# encoder-mjf.net
KiCad netlist of a schematic drawn in Altium Designer
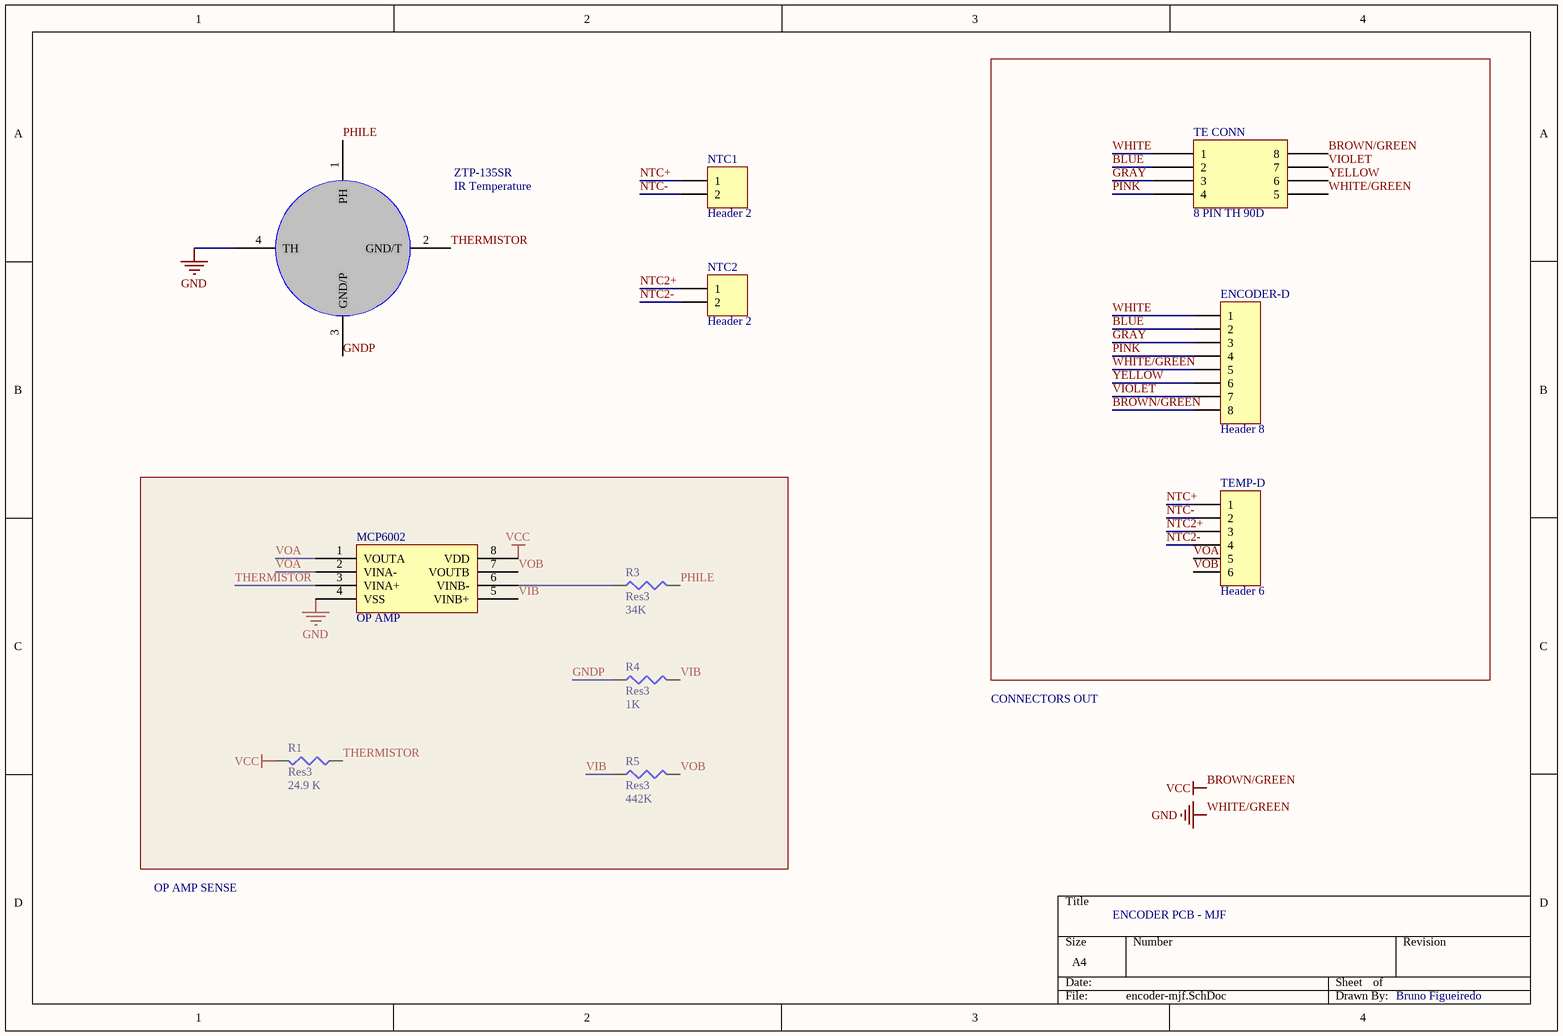
[diagram p0: encoder-mjf.SchDoc]

(export (version "E")
  (design (tool "Eeschema 10.0.6"))
  (components
    (comp (ref "ENCODER-D")
      (value "Header 8")
      (footprint "HDR1X8")
      (description "Header, 8-Pin")
      (fields (field (name "PUBLISHER") "Altium Limited"))
      (libsource (lib "Miscellaneous Connectors") (part "Header 8"))
    )
    (comp (ref "MCP6002")
      (value "OP AMP")
      (footprint "DIP-8")
      (libsource (lib "encoder-mjf") (part "MCP6002-I/P"))
    )
    (comp (ref "NTC1")
      (value "Header 2")
      (footprint "HDR1X2")
      (description "Header, 2-Pin")
      (fields (field (name "PUBLISHER") "Altium Limited"))
      (libsource (lib "Miscellaneous Connectors") (part "Header 2"))
    )
    (comp (ref "NTC2")
      (value "Header 2")
      (footprint "HDR1X2")
      (description "Header, 2-Pin")
      (fields (field (name "PUBLISHER") "Altium Limited"))
      (libsource (lib "Miscellaneous Connectors") (part "Header 2"))
    )
    (comp (ref "R1")
      (value "Res3")
      (footprint "J1-0603")
      (description "Resistor")
      (fields (field (name "ALTIUM_VALUE") "24.9 K") (field (name "PUBLISHER") "Altium Limited"))
      (libsource (lib "Miscellaneous Devices") (part "Res3"))
    )
    (comp (ref "R3")
      (value "Res3")
      (footprint "J1-0603")
      (description "Resistor")
      (fields (field (name "ALTIUM_VALUE") "34K") (field (name "PUBLISHER") "Altium Limited"))
      (libsource (lib "Miscellaneous Devices") (part "Res3"))
    )
    (comp (ref "R4")
      (value "Res3")
      (footprint "J1-0603")
      (description "Resistor")
      (fields (field (name "ALTIUM_VALUE") "1K") (field (name "PUBLISHER") "Altium Limited"))
      (libsource (lib "Miscellaneous Devices") (part "Res3"))
    )
    (comp (ref "R5")
      (value "Res3")
      (footprint "C1206")
      (description "Resistor")
      (fields (field (name "ALTIUM_VALUE") "442K") (field (name "PUBLISHER") "Altium Limited"))
      (libsource (lib "Miscellaneous Devices") (part "Res3"))
    )
    (comp (ref "TE CONN")
      (value "8 PIN TH 90D")
      (footprint "NG_CD_2172077")
      (libsource (lib "encoder-mjf") (part "NG-CD-2172077"))
    )
    (comp (ref "TEMP-D")
      (value "Header 6")
      (footprint "HDR1X6")
      (description "Header, 6-Pin")
      (fields (field (name "PUBLISHER") "Altium Limited"))
      (libsource (lib "Miscellaneous Connectors") (part "Header 6"))
    )
    (comp (ref "ZTP-135SR")
      (value "IR Temperature")
      (footprint "ZTP-135SR")
      (description "Thermistor + Thermophile")
      (libsource (lib "encoder-mjf") (part "ZTP-135SR"))
    )
  )
  (nets
    (net (code "1") (name "/BLUE") (class "Default")
      (node (ref "ENCODER-D") (pin "2") (pinfunction "2_2") (pintype "passive"))
      (node (ref "TE CONN") (pin "2") (pinfunction "2_2") (pintype "passive"))
    )
    (net (code "2") (name "/GNDP") (class "Default")
      (node (ref "R4") (pin "1") (pinfunction "1_1") (pintype "passive"))
      (node (ref "ZTP-135SR") (pin "3") (pinfunction "GND/P_3") (pintype "passive"))
    )
    (net (code "3") (name "/GRAY") (class "Default")
      (node (ref "ENCODER-D") (pin "3") (pinfunction "3_3") (pintype "passive"))
      (node (ref "TE CONN") (pin "3") (pinfunction "3_3") (pintype "passive"))
    )
    (net (code "4") (name "/NTC+") (class "Default")
      (node (ref "NTC1") (pin "1") (pinfunction "1_1") (pintype "passive"))
      (node (ref "TEMP-D") (pin "1") (pinfunction "1_1") (pintype "passive"))
    )
    (net (code "5") (name "/NTC-") (class "Default")
      (node (ref "NTC1") (pin "2") (pinfunction "2_2") (pintype "passive"))
      (node (ref "TEMP-D") (pin "2") (pinfunction "2_2") (pintype "passive"))
    )
    (net (code "6") (name "/NTC2+") (class "Default")
      (node (ref "NTC2") (pin "1") (pinfunction "1_1") (pintype "passive"))
      (node (ref "TEMP-D") (pin "3") (pinfunction "3_3") (pintype "passive"))
    )
    (net (code "7") (name "/NTC2-") (class "Default")
      (node (ref "NTC2") (pin "2") (pinfunction "2_2") (pintype "passive"))
      (node (ref "TEMP-D") (pin "4") (pinfunction "4_4") (pintype "passive"))
    )
    (net (code "8") (name "/PHILE") (class "Default")
      (node (ref "R3") (pin "2") (pinfunction "2_2") (pintype "passive"))
      (node (ref "ZTP-135SR") (pin "1") (pinfunction "PH_1") (pintype "passive"))
    )
    (net (code "9") (name "/PINK") (class "Default")
      (node (ref "ENCODER-D") (pin "4") (pinfunction "4_4") (pintype "passive"))
      (node (ref "TE CONN") (pin "4") (pinfunction "4_4") (pintype "passive"))
    )
    (net (code "10") (name "/THERMISTOR") (class "Default")
      (node (ref "MCP6002") (pin "3") (pinfunction "VINA+_3") (pintype "passive"))
      (node (ref "R1") (pin "1") (pinfunction "1_1") (pintype "passive"))
      (node (ref "ZTP-135SR") (pin "2") (pinfunction "GND/T_2") (pintype "passive"))
    )
    (net (code "11") (name "/VIB") (class "Default")
      (node (ref "MCP6002") (pin "5") (pinfunction "VINB+_5") (pintype "passive"))
      (node (ref "R4") (pin "2") (pinfunction "2_2") (pintype "passive"))
      (node (ref "R5") (pin "1") (pinfunction "1_1") (pintype "passive"))
    )
    (net (code "12") (name "/VIOLET") (class "Default")
      (node (ref "ENCODER-D") (pin "7") (pinfunction "7_7") (pintype "passive"))
      (node (ref "TE CONN") (pin "7") (pinfunction "7_7") (pintype "passive"))
    )
    (net (code "13") (name "/VOA") (class "Default")
      (node (ref "MCP6002") (pin "1") (pinfunction "VOUTA_1") (pintype "passive"))
      (node (ref "MCP6002") (pin "2") (pinfunction "VINA-_2") (pintype "passive"))
      (node (ref "TEMP-D") (pin "5") (pinfunction "5_5") (pintype "passive"))
    )
    (net (code "14") (name "/VOB") (class "Default")
      (node (ref "MCP6002") (pin "7") (pinfunction "VOUTB_7") (pintype "passive"))
      (node (ref "R5") (pin "2") (pinfunction "2_2") (pintype "passive"))
      (node (ref "TEMP-D") (pin "6") (pinfunction "6_6") (pintype "passive"))
    )
    (net (code "15") (name "/WHITE") (class "Default")
      (node (ref "ENCODER-D") (pin "1") (pinfunction "1_1") (pintype "passive"))
      (node (ref "TE CONN") (pin "1") (pinfunction "1_1") (pintype "passive"))
    )
    (net (code "16") (name "/YELLOW") (class "Default")
      (node (ref "ENCODER-D") (pin "6") (pinfunction "6_6") (pintype "passive"))
      (node (ref "TE CONN") (pin "6") (pinfunction "6_6") (pintype "passive"))
    )
    (net (code "17") (name "GND") (class "Default")
      (node (ref "ENCODER-D") (pin "5") (pinfunction "5_5") (pintype "passive"))
      (node (ref "MCP6002") (pin "4") (pinfunction "VSS_4") (pintype "passive"))
      (node (ref "TE CONN") (pin "5") (pinfunction "5_5") (pintype "passive"))
      (node (ref "ZTP-135SR") (pin "4") (pinfunction "TH_4") (pintype "passive"))
    )
    (net (code "18") (name "Net-(MCP6002-VINB-)") (class "Default")
      (node (ref "MCP6002") (pin "6") (pinfunction "VINB-_6") (pintype "passive"))
      (node (ref "R3") (pin "1") (pinfunction "1_1") (pintype "passive"))
    )
    (net (code "19") (name "VCC") (class "Default")
      (node (ref "ENCODER-D") (pin "8") (pinfunction "8_8") (pintype "passive"))
      (node (ref "MCP6002") (pin "8") (pinfunction "VDD_8") (pintype "passive"))
      (node (ref "R1") (pin "2") (pinfunction "2_2") (pintype "passive"))
      (node (ref "TE CONN") (pin "8") (pinfunction "8_8") (pintype "passive"))
    )
  )
)
